# M514H.net
KiCad netlist of a schematic drawn in EAGLE
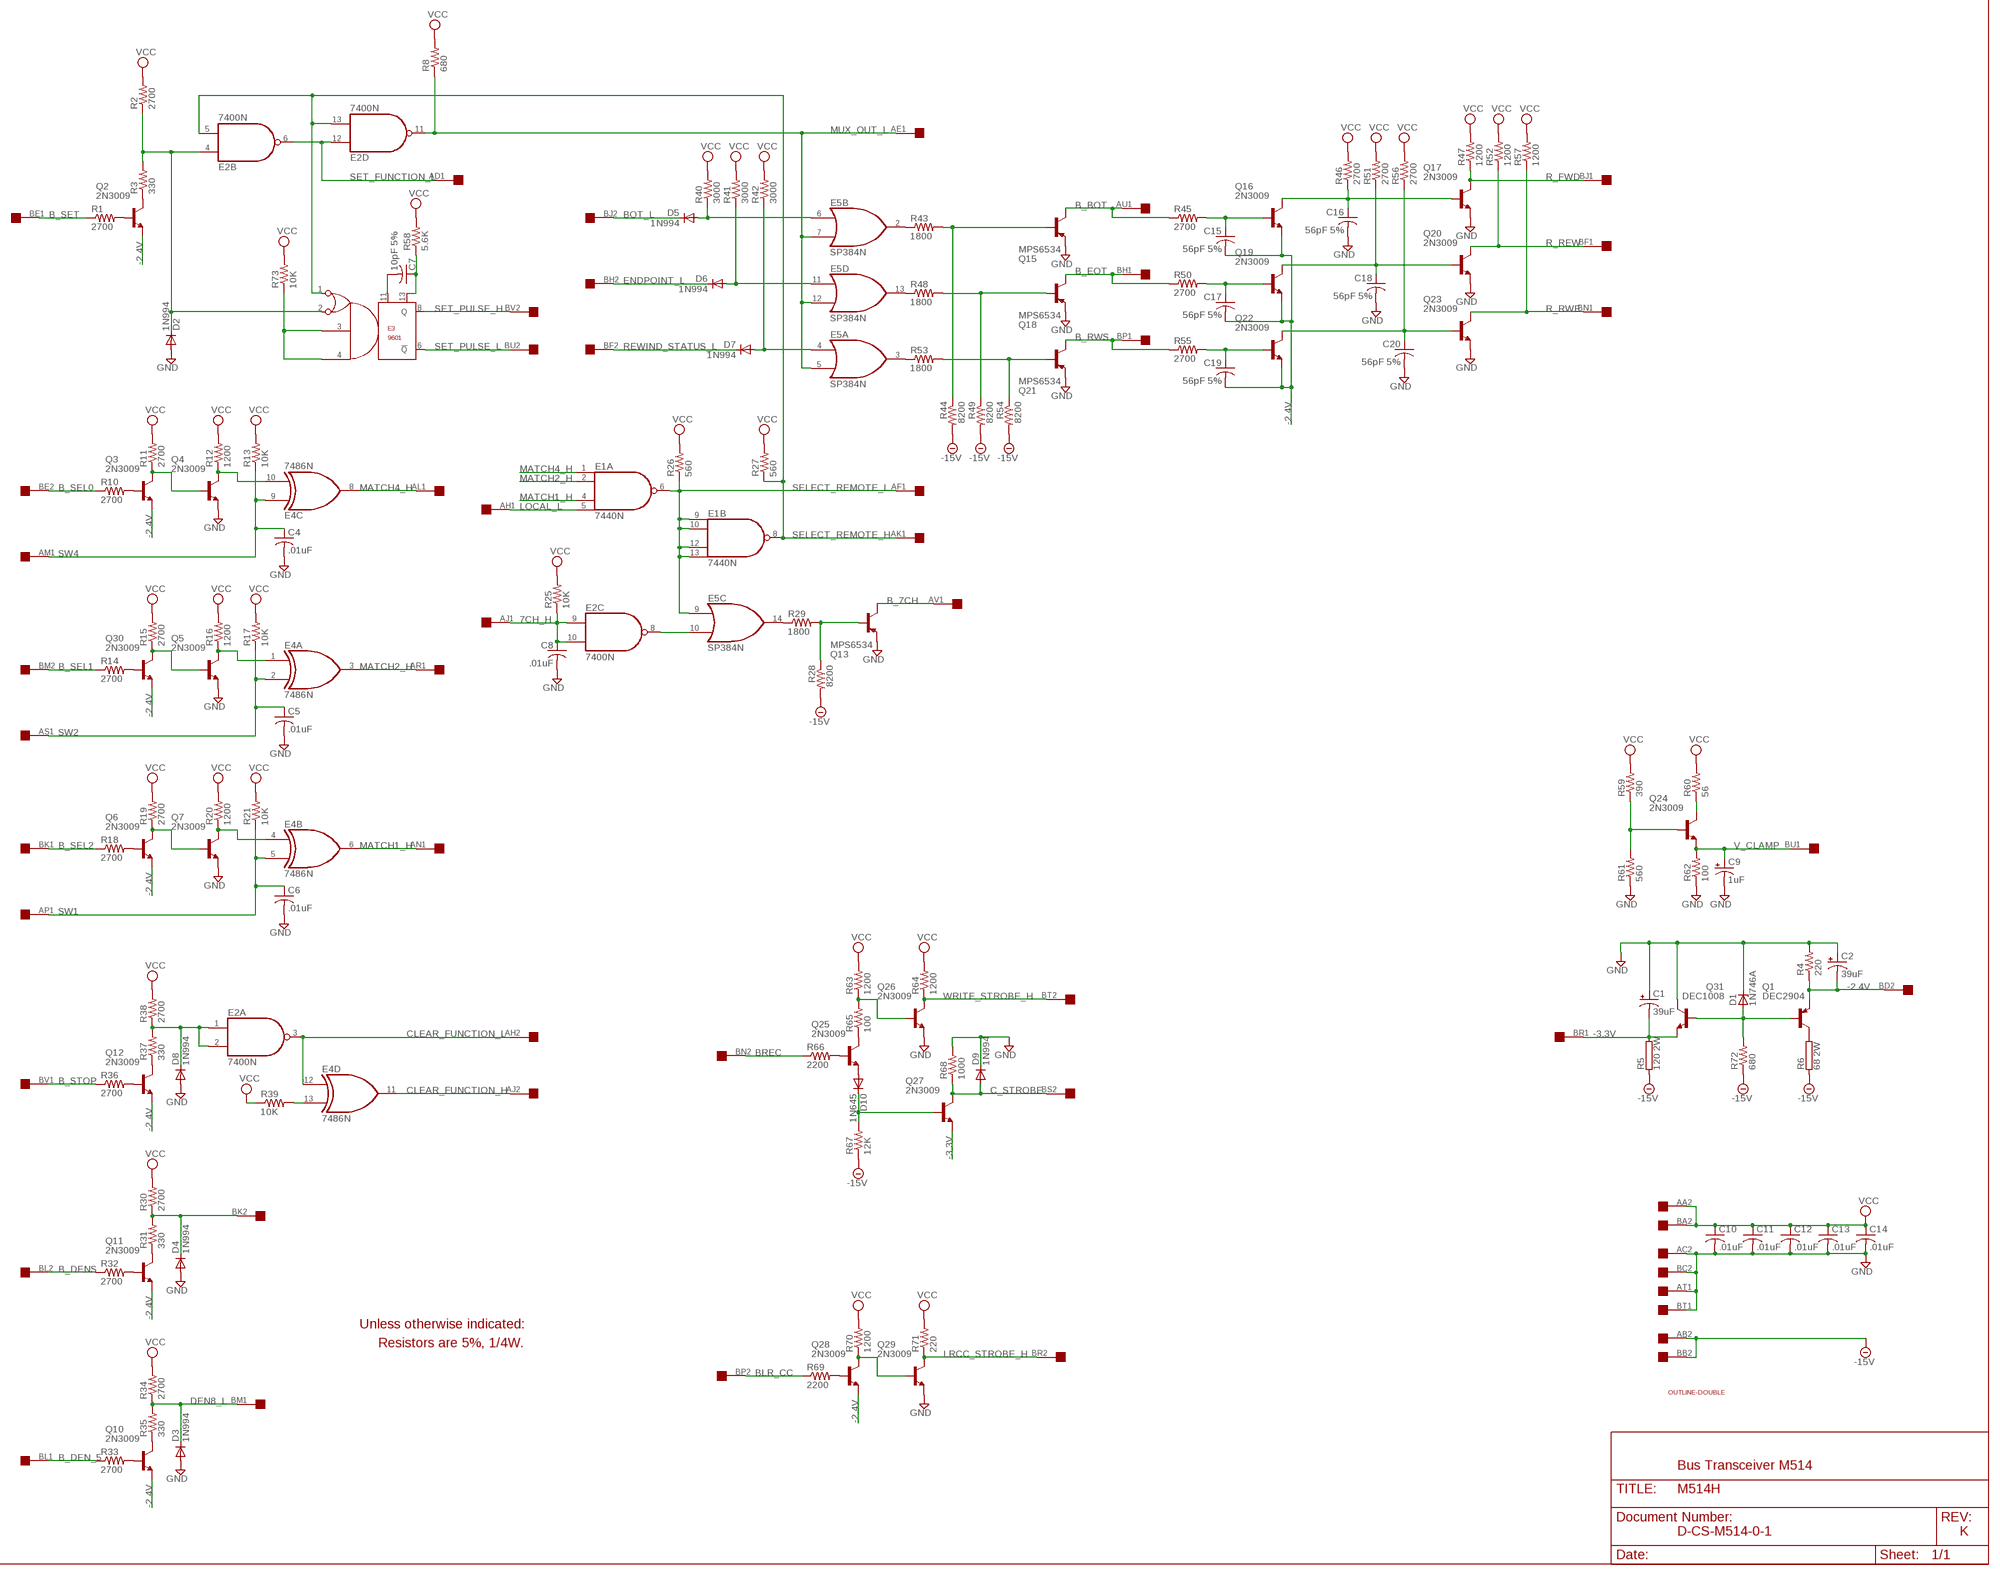
[diagram p0: schematic, sheet 1]

(export (version "E")
  (design (tool "Eeschema 10.0.6"))
  (components
    (comp (ref "C1")
      (value "39uF")
      (footprint "eagle-import:E12-8")
      (libsource (lib "eagle-import") (part "CPOL-USE20-8AXIAL"))
    )
    (comp (ref "C2")
      (value "39uF")
      (footprint "eagle-import:E12-8")
      (libsource (lib "eagle-import") (part "CPOL-USE20-8AXIAL"))
    )
    (comp (ref "C4")
      (value ".01uF")
      (footprint "eagle-import:C050-025X075")
      (libsource (lib "eagle-import") (part "C-US050-025X075"))
    )
    (comp (ref "C5")
      (value ".01uF")
      (footprint "eagle-import:C050-025X075")
      (libsource (lib "eagle-import") (part "C-US050-025X075"))
    )
    (comp (ref "C6")
      (value ".01uF")
      (footprint "eagle-import:C050-025X075")
      (libsource (lib "eagle-import") (part "C-US050-025X075"))
    )
    (comp (ref "C7")
      (value "10pF 5%")
      (footprint "eagle-import:C050-025X075")
      (libsource (lib "eagle-import") (part "C-US050-025X075"))
    )
    (comp (ref "C8")
      (value ".01uF")
      (footprint "eagle-import:C050-025X075")
      (libsource (lib "eagle-import") (part "C-US050-025X075"))
    )
    (comp (ref "C9")
      (value "1uF")
      (footprint "eagle-import:E15-5")
      (libsource (lib "eagle-import") (part "CPOL-USE15-5AXIAL"))
    )
    (comp (ref "C10")
      (value ".01uF")
      (footprint "eagle-import:C050-025X075")
      (libsource (lib "eagle-import") (part "C-US050-025X075"))
    )
    (comp (ref "C11")
      (value ".01uF")
      (footprint "eagle-import:C050-025X075")
      (libsource (lib "eagle-import") (part "C-US050-025X075"))
    )
    (comp (ref "C12")
      (value ".01uF")
      (footprint "eagle-import:C050-025X075")
      (libsource (lib "eagle-import") (part "C-US050-025X075"))
    )
    (comp (ref "C13")
      (value ".01uF")
      (footprint "eagle-import:C050-025X075")
      (libsource (lib "eagle-import") (part "C-US050-025X075"))
    )
    (comp (ref "C14")
      (value ".01uF")
      (footprint "eagle-import:C050-025X075")
      (libsource (lib "eagle-import") (part "C-US050-025X075"))
    )
    (comp (ref "C15")
      (value "56pF 5%")
      (footprint "eagle-import:C050-025X075")
      (libsource (lib "eagle-import") (part "C-US050-025X075"))
    )
    (comp (ref "C16")
      (value "56pF 5%")
      (footprint "eagle-import:C050-025X075")
      (libsource (lib "eagle-import") (part "C-US050-025X075"))
    )
    (comp (ref "C17")
      (value "56pF 5%")
      (footprint "eagle-import:C050-025X075")
      (libsource (lib "eagle-import") (part "C-US050-025X075"))
    )
    (comp (ref "C18")
      (value "56pF 5%")
      (footprint "eagle-import:C050-025X075")
      (libsource (lib "eagle-import") (part "C-US050-025X075"))
    )
    (comp (ref "C19")
      (value "56pF 5%")
      (footprint "eagle-import:C050-025X075")
      (libsource (lib "eagle-import") (part "C-US050-025X075"))
    )
    (comp (ref "C20")
      (value "56pF 5%")
      (footprint "eagle-import:C050-025X075")
      (libsource (lib "eagle-import") (part "C-US050-025X075"))
    )
    (comp (ref "D1")
      (value "1N746A")
      (footprint "eagle-import:DO35Z10")
      (libsource (lib "eagle-import") (part "ZENER-DIODEDO35Z10"))
    )
    (comp (ref "D2")
      (value "1N994")
      (footprint "eagle-import:DO35-10")
      (libsource (lib "eagle-import") (part "1N4148DO35-10"))
    )
    (comp (ref "D3")
      (value "1N994")
      (footprint "eagle-import:DO35-10")
      (libsource (lib "eagle-import") (part "1N4148DO35-10"))
    )
    (comp (ref "D4")
      (value "1N994")
      (footprint "eagle-import:DO35-10")
      (libsource (lib "eagle-import") (part "1N4148DO35-10"))
    )
    (comp (ref "D5")
      (value "1N994")
      (footprint "eagle-import:DO35-10")
      (libsource (lib "eagle-import") (part "1N4148DO35-10"))
    )
    (comp (ref "D6")
      (value "1N994")
      (footprint "eagle-import:DO35-10")
      (libsource (lib "eagle-import") (part "1N4148DO35-10"))
    )
    (comp (ref "D7")
      (value "1N994")
      (footprint "eagle-import:DO35-10")
      (libsource (lib "eagle-import") (part "1N4148DO35-10"))
    )
    (comp (ref "D8")
      (value "1N994")
      (footprint "eagle-import:DO35-10")
      (libsource (lib "eagle-import") (part "1N4148DO35-10"))
    )
    (comp (ref "D9")
      (value "1N994")
      (footprint "eagle-import:DO35-10")
      (libsource (lib "eagle-import") (part "1N4148DO35-10"))
    )
    (comp (ref "D10")
      (value "1N645")
      (footprint "eagle-import:DO35-10")
      (libsource (lib "eagle-import") (part "1N4148DO35-10"))
    )
    (comp (ref "E1")
      (value "7440N")
      (footprint "eagle-import:DIL14")
      (libsource (lib "eagle-import") (part "7420NS"))
    )
    (comp (ref "E2")
      (value "7400N")
      (footprint "eagle-import:DIL14")
      (libsource (lib "eagle-import") (part "7400N"))
    )
    (comp (ref "E3")
      (value "9601")
      (footprint "eagle-import:DIL14")
      (libsource (lib "eagle-import") (part "9601"))
    )
    (comp (ref "E4")
      (value "7486N")
      (footprint "eagle-import:DIL14")
      (libsource (lib "eagle-import") (part "7486N"))
    )
    (comp (ref "E5")
      (value "SP384N")
      (footprint "eagle-import:DIL14")
      (libsource (lib "eagle-import") (part "SP384N"))
    )
    (comp (ref "Q1")
      (value "DEC2904")
      (footprint "eagle-import:TO39")
      (libsource (lib "eagle-import") (part "2N3635"))
    )
    (comp (ref "Q2")
      (value "2N3009")
      (footprint "eagle-import:TO5")
      (libsource (lib "eagle-import") (part "2N3439"))
    )
    (comp (ref "Q3")
      (value "2N3009")
      (footprint "eagle-import:TO5")
      (libsource (lib "eagle-import") (part "2N3439"))
    )
    (comp (ref "Q4")
      (value "2N3009")
      (footprint "eagle-import:TO5")
      (libsource (lib "eagle-import") (part "2N3439"))
    )
    (comp (ref "Q5")
      (value "2N3009")
      (footprint "eagle-import:TO5")
      (libsource (lib "eagle-import") (part "2N3439"))
    )
    (comp (ref "Q6")
      (value "2N3009")
      (footprint "eagle-import:TO5")
      (libsource (lib "eagle-import") (part "2N3439"))
    )
    (comp (ref "Q7")
      (value "2N3009")
      (footprint "eagle-import:TO5")
      (libsource (lib "eagle-import") (part "2N3439"))
    )
    (comp (ref "Q10")
      (value "2N3009")
      (footprint "eagle-import:TO5")
      (libsource (lib "eagle-import") (part "2N3439"))
    )
    (comp (ref "Q11")
      (value "2N3009")
      (footprint "eagle-import:TO5")
      (libsource (lib "eagle-import") (part "2N3439"))
    )
    (comp (ref "Q12")
      (value "2N3009")
      (footprint "eagle-import:TO5")
      (libsource (lib "eagle-import") (part "2N3439"))
    )
    (comp (ref "Q13")
      (value "MPS6534")
      (footprint "eagle-import:TO39")
      (libsource (lib "eagle-import") (part "2N3635"))
    )
    (comp (ref "Q15")
      (value "MPS6534")
      (footprint "eagle-import:TO39")
      (libsource (lib "eagle-import") (part "2N3635"))
    )
    (comp (ref "Q16")
      (value "2N3009")
      (footprint "eagle-import:TO5")
      (libsource (lib "eagle-import") (part "2N3439"))
    )
    (comp (ref "Q17")
      (value "2N3009")
      (footprint "eagle-import:TO5")
      (libsource (lib "eagle-import") (part "2N3439"))
    )
    (comp (ref "Q18")
      (value "MPS6534")
      (footprint "eagle-import:TO39")
      (libsource (lib "eagle-import") (part "2N3635"))
    )
    (comp (ref "Q19")
      (value "2N3009")
      (footprint "eagle-import:TO5")
      (libsource (lib "eagle-import") (part "2N3439"))
    )
    (comp (ref "Q20")
      (value "2N3009")
      (footprint "eagle-import:TO5")
      (libsource (lib "eagle-import") (part "2N3439"))
    )
    (comp (ref "Q21")
      (value "MPS6534")
      (footprint "eagle-import:TO39")
      (libsource (lib "eagle-import") (part "2N3635"))
    )
    (comp (ref "Q22")
      (value "2N3009")
      (footprint "eagle-import:TO5")
      (libsource (lib "eagle-import") (part "2N3439"))
    )
    (comp (ref "Q23")
      (value "2N3009")
      (footprint "eagle-import:TO5")
      (libsource (lib "eagle-import") (part "2N3439"))
    )
    (comp (ref "Q24")
      (value "2N3009")
      (footprint "eagle-import:TO5")
      (libsource (lib "eagle-import") (part "2N3439"))
    )
    (comp (ref "Q25")
      (value "2N3009")
      (footprint "eagle-import:TO5")
      (libsource (lib "eagle-import") (part "2N3439"))
    )
    (comp (ref "Q26")
      (value "2N3009")
      (footprint "eagle-import:TO5")
      (libsource (lib "eagle-import") (part "2N3439"))
    )
    (comp (ref "Q27")
      (value "2N3009")
      (footprint "eagle-import:TO5")
      (libsource (lib "eagle-import") (part "2N3439"))
    )
    (comp (ref "Q28")
      (value "2N3009")
      (footprint "eagle-import:TO5")
      (libsource (lib "eagle-import") (part "2N3439"))
    )
    (comp (ref "Q29")
      (value "2N3009")
      (footprint "eagle-import:TO5")
      (libsource (lib "eagle-import") (part "2N3439"))
    )
    (comp (ref "Q30")
      (value "2N3009")
      (footprint "eagle-import:TO5")
      (libsource (lib "eagle-import") (part "2N3439"))
    )
    (comp (ref "Q31")
      (value "DEC1008")
      (footprint "eagle-import:TO5")
      (libsource (lib "eagle-import") (part "2N3439"))
    )
    (comp (ref "R1")
      (value "2700")
      (footprint "eagle-import:0207_10")
      (libsource (lib "eagle-import") (part "R-US_0207/10"))
    )
    (comp (ref "R2")
      (value "2700")
      (footprint "eagle-import:0207_10")
      (libsource (lib "eagle-import") (part "R-US_0207/10"))
    )
    (comp (ref "R3")
      (value "330")
      (footprint "eagle-import:0207_10")
      (libsource (lib "eagle-import") (part "R-US_0207/10"))
    )
    (comp (ref "R4")
      (value "220")
      (footprint "eagle-import:0207_10")
      (libsource (lib "eagle-import") (part "R-US_0207/10"))
    )
    (comp (ref "R5")
      (value "120 2W")
      (footprint "eagle-import:KH206-8")
      (libsource (lib "eagle-import") (part "RKH206-8"))
    )
    (comp (ref "R6")
      (value "68 2W")
      (footprint "eagle-import:KH206-8")
      (libsource (lib "eagle-import") (part "RKH206-8"))
    )
    (comp (ref "R8")
      (value "680")
      (footprint "eagle-import:0207_10")
      (libsource (lib "eagle-import") (part "R-US_0207/10"))
    )
    (comp (ref "R10")
      (value "2700")
      (footprint "eagle-import:0207_10")
      (libsource (lib "eagle-import") (part "R-US_0207/10"))
    )
    (comp (ref "R11")
      (value "2700")
      (footprint "eagle-import:0207_10")
      (libsource (lib "eagle-import") (part "R-US_0207/10"))
    )
    (comp (ref "R12")
      (value "1200")
      (footprint "eagle-import:0207_10")
      (libsource (lib "eagle-import") (part "R-US_0207/10"))
    )
    (comp (ref "R13")
      (value "10K")
      (footprint "eagle-import:0207_10")
      (libsource (lib "eagle-import") (part "R-US_0207/10"))
    )
    (comp (ref "R14")
      (value "2700")
      (footprint "eagle-import:0207_10")
      (libsource (lib "eagle-import") (part "R-US_0207/10"))
    )
    (comp (ref "R15")
      (value "2700")
      (footprint "eagle-import:0207_10")
      (libsource (lib "eagle-import") (part "R-US_0207/10"))
    )
    (comp (ref "R16")
      (value "1200")
      (footprint "eagle-import:0207_10")
      (libsource (lib "eagle-import") (part "R-US_0207/10"))
    )
    (comp (ref "R17")
      (value "10K")
      (footprint "eagle-import:0207_10")
      (libsource (lib "eagle-import") (part "R-US_0207/10"))
    )
    (comp (ref "R18")
      (value "2700")
      (footprint "eagle-import:0207_10")
      (libsource (lib "eagle-import") (part "R-US_0207/10"))
    )
    (comp (ref "R19")
      (value "2700")
      (footprint "eagle-import:0207_10")
      (libsource (lib "eagle-import") (part "R-US_0207/10"))
    )
    (comp (ref "R20")
      (value "1200")
      (footprint "eagle-import:0207_10")
      (libsource (lib "eagle-import") (part "R-US_0207/10"))
    )
    (comp (ref "R21")
      (value "10K")
      (footprint "eagle-import:0207_10")
      (libsource (lib "eagle-import") (part "R-US_0207/10"))
    )
    (comp (ref "R25")
      (value "10K")
      (footprint "eagle-import:0207_10")
      (libsource (lib "eagle-import") (part "R-US_0207/10"))
    )
    (comp (ref "R26")
      (value "560")
      (footprint "eagle-import:0207_10")
      (libsource (lib "eagle-import") (part "R-US_0207/10"))
    )
    (comp (ref "R27")
      (value "560")
      (footprint "eagle-import:0207_10")
      (libsource (lib "eagle-import") (part "R-US_0207/10"))
    )
    (comp (ref "R28")
      (value "8200")
      (footprint "eagle-import:0207_10")
      (libsource (lib "eagle-import") (part "R-US_0207/10"))
    )
    (comp (ref "R29")
      (value "1800")
      (footprint "eagle-import:0207_10")
      (libsource (lib "eagle-import") (part "R-US_0207/10"))
    )
    (comp (ref "R30")
      (value "2700")
      (footprint "eagle-import:0207_10")
      (libsource (lib "eagle-import") (part "R-US_0207/10"))
    )
    (comp (ref "R31")
      (value "330")
      (footprint "eagle-import:0207_10")
      (libsource (lib "eagle-import") (part "R-US_0207/10"))
    )
    (comp (ref "R32")
      (value "2700")
      (footprint "eagle-import:0207_10")
      (libsource (lib "eagle-import") (part "R-US_0207/10"))
    )
    (comp (ref "R33")
      (value "2700")
      (footprint "eagle-import:0207_10")
      (libsource (lib "eagle-import") (part "R-US_0207/10"))
    )
    (comp (ref "R34")
      (value "2700")
      (footprint "eagle-import:0207_10")
      (libsource (lib "eagle-import") (part "R-US_0207/10"))
    )
    (comp (ref "R35")
      (value "330")
      (footprint "eagle-import:0207_10")
      (libsource (lib "eagle-import") (part "R-US_0207/10"))
    )
    (comp (ref "R36")
      (value "2700")
      (footprint "eagle-import:0207_10")
      (libsource (lib "eagle-import") (part "R-US_0207/10"))
    )
    (comp (ref "R37")
      (value "330")
      (footprint "eagle-import:0207_10")
      (libsource (lib "eagle-import") (part "R-US_0207/10"))
    )
    (comp (ref "R38")
      (value "2700")
      (footprint "eagle-import:0207_10")
      (libsource (lib "eagle-import") (part "R-US_0207/10"))
    )
    (comp (ref "R39")
      (value "10K")
      (footprint "eagle-import:0207_10")
      (libsource (lib "eagle-import") (part "R-US_0207/10"))
    )
    (comp (ref "R40")
      (value "3000")
      (footprint "eagle-import:0207_10")
      (libsource (lib "eagle-import") (part "R-US_0207/10"))
    )
    (comp (ref "R41")
      (value "3000")
      (footprint "eagle-import:0207_10")
      (libsource (lib "eagle-import") (part "R-US_0207/10"))
    )
    (comp (ref "R42")
      (value "3000")
      (footprint "eagle-import:0207_10")
      (libsource (lib "eagle-import") (part "R-US_0207/10"))
    )
    (comp (ref "R43")
      (value "1800")
      (footprint "eagle-import:0207_10")
      (libsource (lib "eagle-import") (part "R-US_0207/10"))
    )
    (comp (ref "R44")
      (value "8200")
      (footprint "eagle-import:0207_10")
      (libsource (lib "eagle-import") (part "R-US_0207/10"))
    )
    (comp (ref "R45")
      (value "2700")
      (footprint "eagle-import:0207_10")
      (libsource (lib "eagle-import") (part "R-US_0207/10"))
    )
    (comp (ref "R46")
      (value "2700")
      (footprint "eagle-import:0207_10")
      (libsource (lib "eagle-import") (part "R-US_0207/10"))
    )
    (comp (ref "R47")
      (value "1200")
      (footprint "eagle-import:0207_10")
      (libsource (lib "eagle-import") (part "R-US_0207/10"))
    )
    (comp (ref "R48")
      (value "1800")
      (footprint "eagle-import:0207_10")
      (libsource (lib "eagle-import") (part "R-US_0207/10"))
    )
    (comp (ref "R49")
      (value "8200")
      (footprint "eagle-import:0207_10")
      (libsource (lib "eagle-import") (part "R-US_0207/10"))
    )
    (comp (ref "R50")
      (value "2700")
      (footprint "eagle-import:0207_10")
      (libsource (lib "eagle-import") (part "R-US_0207/10"))
    )
    (comp (ref "R51")
      (value "2700")
      (footprint "eagle-import:0207_10")
      (libsource (lib "eagle-import") (part "R-US_0207/10"))
    )
    (comp (ref "R52")
      (value "1200")
      (footprint "eagle-import:0207_10")
      (libsource (lib "eagle-import") (part "R-US_0207/10"))
    )
    (comp (ref "R53")
      (value "1800")
      (footprint "eagle-import:0207_10")
      (libsource (lib "eagle-import") (part "R-US_0207/10"))
    )
    (comp (ref "R54")
      (value "8200")
      (footprint "eagle-import:0207_10")
      (libsource (lib "eagle-import") (part "R-US_0207/10"))
    )
    (comp (ref "R55")
      (value "2700")
      (footprint "eagle-import:0207_10")
      (libsource (lib "eagle-import") (part "R-US_0207/10"))
    )
    (comp (ref "R56")
      (value "2700")
      (footprint "eagle-import:0207_10")
      (libsource (lib "eagle-import") (part "R-US_0207/10"))
    )
    (comp (ref "R57")
      (value "1200")
      (footprint "eagle-import:0207_10")
      (libsource (lib "eagle-import") (part "R-US_0207/10"))
    )
    (comp (ref "R58")
      (value "5.6K")
      (footprint "eagle-import:0207_10")
      (libsource (lib "eagle-import") (part "R-US_0207/10"))
    )
    (comp (ref "R59")
      (value "390")
      (footprint "eagle-import:0207_10")
      (libsource (lib "eagle-import") (part "R-US_0207/10"))
    )
    (comp (ref "R60")
      (value "56")
      (footprint "eagle-import:0207_10")
      (libsource (lib "eagle-import") (part "R-US_0207/10"))
    )
    (comp (ref "R61")
      (value "560")
      (footprint "eagle-import:0207_10")
      (libsource (lib "eagle-import") (part "R-US_0207/10"))
    )
    (comp (ref "R62")
      (value "100")
      (footprint "eagle-import:0207_10")
      (libsource (lib "eagle-import") (part "R-US_0207/10"))
    )
    (comp (ref "R63")
      (value "1200")
      (footprint "eagle-import:0207_10")
      (libsource (lib "eagle-import") (part "R-US_0207/10"))
    )
    (comp (ref "R64")
      (value "1200")
      (footprint "eagle-import:0207_10")
      (libsource (lib "eagle-import") (part "R-US_0207/10"))
    )
    (comp (ref "R65")
      (value "100")
      (footprint "eagle-import:0207_10")
      (libsource (lib "eagle-import") (part "R-US_0207/10"))
    )
    (comp (ref "R66")
      (value "2200")
      (footprint "eagle-import:0207_10")
      (libsource (lib "eagle-import") (part "R-US_0207/10"))
    )
    (comp (ref "R67")
      (value "12K")
      (footprint "eagle-import:0207_10")
      (libsource (lib "eagle-import") (part "R-US_0207/10"))
    )
    (comp (ref "R68")
      (value "1000")
      (footprint "eagle-import:0207_10")
      (libsource (lib "eagle-import") (part "R-US_0207/10"))
    )
    (comp (ref "R69")
      (value "2200")
      (footprint "eagle-import:0207_10")
      (libsource (lib "eagle-import") (part "R-US_0207/10"))
    )
    (comp (ref "R70")
      (value "1200")
      (footprint "eagle-import:0207_10")
      (libsource (lib "eagle-import") (part "R-US_0207/10"))
    )
    (comp (ref "R71")
      (value "220")
      (footprint "eagle-import:0207_10")
      (libsource (lib "eagle-import") (part "R-US_0207/10"))
    )
    (comp (ref "R72")
      (value "680")
      (footprint "eagle-import:0207_10")
      (libsource (lib "eagle-import") (part "R-US_0207/10"))
    )
    (comp (ref "R73")
      (value "10K")
      (footprint "eagle-import:0207_10")
      (libsource (lib "eagle-import") (part "R-US_0207/10"))
    )
    (comp (ref "U$1")
      (value "DOUBLE")
      (footprint "eagle-import:EDGE-CON4")
      (libsource (lib "eagle-import") (part "DOUBLE"))
    )
    (comp (ref "U$2")
      (value "OUTLINE-DOUBLE")
      (footprint "eagle-import:DOUBLE")
      (libsource (lib "eagle-import") (part "OUTLINE-DOUBLE"))
    )
  )
  (nets
    (net (code "1") (name "-15V") (class "Default")
      (node (ref "R28") (pin "2") (pinfunction "2_2") (pintype "passive"))
      (node (ref "R44") (pin "2") (pinfunction "2_2") (pintype "passive"))
      (node (ref "R49") (pin "2") (pinfunction "2_2") (pintype "passive"))
      (node (ref "R5") (pin "1") (pinfunction "1_1") (pintype "passive"))
      (node (ref "R54") (pin "2") (pinfunction "2_2") (pintype "passive"))
      (node (ref "R6") (pin "1") (pinfunction "1_1") (pintype "passive"))
      (node (ref "R67") (pin "1") (pinfunction "1_1") (pintype "passive"))
      (node (ref "R72") (pin "1") (pinfunction "1_1") (pintype "passive"))
      (node (ref "U$1") (pin "AB2") (pinfunction "1_AB2") (pintype "bidirectional"))
      (node (ref "U$1") (pin "BB2") (pinfunction "1_BB2") (pintype "bidirectional"))
    )
    (net (code "2") (name "/-2.4V") (class "Default")
      (node (ref "C15") (pin "2") (pinfunction "2_2") (pintype "passive"))
      (node (ref "C17") (pin "2") (pinfunction "2_2") (pintype "passive"))
      (node (ref "C19") (pin "2") (pinfunction "2_2") (pintype "passive"))
      (node (ref "C2") (pin "-") (pinfunction "-_-") (pintype "passive"))
      (node (ref "Q1") (pin "1") (pinfunction "E_1") (pintype "passive"))
      (node (ref "Q10") (pin "1") (pinfunction "E_1") (pintype "passive"))
      (node (ref "Q11") (pin "1") (pinfunction "E_1") (pintype "passive"))
      (node (ref "Q12") (pin "1") (pinfunction "E_1") (pintype "passive"))
      (node (ref "Q16") (pin "1") (pinfunction "E_1") (pintype "passive"))
      (node (ref "Q19") (pin "1") (pinfunction "E_1") (pintype "passive"))
      (node (ref "Q2") (pin "1") (pinfunction "E_1") (pintype "passive"))
      (node (ref "Q22") (pin "1") (pinfunction "E_1") (pintype "passive"))
      (node (ref "Q28") (pin "1") (pinfunction "E_1") (pintype "passive"))
      (node (ref "Q3") (pin "1") (pinfunction "E_1") (pintype "passive"))
      (node (ref "Q30") (pin "1") (pinfunction "E_1") (pintype "passive"))
      (node (ref "Q6") (pin "1") (pinfunction "E_1") (pintype "passive"))
      (node (ref "R4") (pin "1") (pinfunction "1_1") (pintype "passive"))
      (node (ref "U$1") (pin "BD2") (pinfunction "1_BD2") (pintype "bidirectional"))
    )
    (net (code "3") (name "/-3.3V") (class "Default")
      (node (ref "C1") (pin "-") (pinfunction "-_-") (pintype "passive"))
      (node (ref "Q27") (pin "1") (pinfunction "E_1") (pintype "passive"))
      (node (ref "Q31") (pin "1") (pinfunction "E_1") (pintype "passive"))
      (node (ref "R5") (pin "2") (pinfunction "2_2") (pintype "passive"))
      (node (ref "U$1") (pin "BR1") (pinfunction "1_BR1") (pintype "bidirectional"))
    )
    (net (code "4") (name "/7CH_H") (class "Default")
      (node (ref "C8") (pin "1") (pinfunction "1_1") (pintype "passive"))
      (node (ref "E2") (pin "10") (pinfunction "I1_10") (pintype "input"))
      (node (ref "E2") (pin "9") (pinfunction "I0_9") (pintype "input"))
      (node (ref "R25") (pin "1") (pinfunction "1_1") (pintype "passive"))
      (node (ref "U$1") (pin "AJ1") (pinfunction "1_AJ1") (pintype "bidirectional"))
    )
    (net (code "5") (name "/BLR_CC") (class "Default")
      (node (ref "R69") (pin "1") (pinfunction "1_1") (pintype "passive"))
      (node (ref "U$1") (pin "BP2") (pinfunction "1_BP2") (pintype "bidirectional"))
    )
    (net (code "6") (name "/BOT_L") (class "Default")
      (node (ref "D5") (pin "C") (pinfunction "C_C") (pintype "passive"))
      (node (ref "U$1") (pin "BJ2") (pinfunction "1_BJ2") (pintype "bidirectional"))
    )
    (net (code "7") (name "/BREC") (class "Default")
      (node (ref "R66") (pin "1") (pinfunction "1_1") (pintype "passive"))
      (node (ref "U$1") (pin "BN2") (pinfunction "1_BN2") (pintype "bidirectional"))
    )
    (net (code "8") (name "/B_7CH") (class "Default")
      (node (ref "Q13") (pin "3") (pinfunction "C_3") (pintype "passive"))
      (node (ref "U$1") (pin "AV1") (pinfunction "1_AV1") (pintype "bidirectional"))
    )
    (net (code "9") (name "/B_BOT") (class "Default")
      (node (ref "Q15") (pin "3") (pinfunction "C_3") (pintype "passive"))
      (node (ref "R45") (pin "1") (pinfunction "1_1") (pintype "passive"))
      (node (ref "U$1") (pin "AU1") (pinfunction "1_AU1") (pintype "bidirectional"))
    )
    (net (code "10") (name "/B_DENS") (class "Default")
      (node (ref "R32") (pin "1") (pinfunction "1_1") (pintype "passive"))
      (node (ref "U$1") (pin "BL2") (pinfunction "1_BL2") (pintype "bidirectional"))
    )
    (net (code "11") (name "/B_DEN_5") (class "Default")
      (node (ref "R33") (pin "1") (pinfunction "1_1") (pintype "passive"))
      (node (ref "U$1") (pin "BL1") (pinfunction "1_BL1") (pintype "bidirectional"))
    )
    (net (code "12") (name "/B_EOT") (class "Default")
      (node (ref "Q18") (pin "3") (pinfunction "C_3") (pintype "passive"))
      (node (ref "R50") (pin "1") (pinfunction "1_1") (pintype "passive"))
      (node (ref "U$1") (pin "BH1") (pinfunction "1_BH1") (pintype "bidirectional"))
    )
    (net (code "13") (name "/B_RWS") (class "Default")
      (node (ref "Q21") (pin "3") (pinfunction "C_3") (pintype "passive"))
      (node (ref "R55") (pin "1") (pinfunction "1_1") (pintype "passive"))
      (node (ref "U$1") (pin "BP1") (pinfunction "1_BP1") (pintype "bidirectional"))
    )
    (net (code "14") (name "/B_SEL0") (class "Default")
      (node (ref "R10") (pin "1") (pinfunction "1_1") (pintype "passive"))
      (node (ref "U$1") (pin "BE2") (pinfunction "1_BE2") (pintype "bidirectional"))
    )
    (net (code "15") (name "/B_SEL1") (class "Default")
      (node (ref "R14") (pin "1") (pinfunction "1_1") (pintype "passive"))
      (node (ref "U$1") (pin "BM2") (pinfunction "1_BM2") (pintype "bidirectional"))
    )
    (net (code "16") (name "/B_SEL2") (class "Default")
      (node (ref "R18") (pin "1") (pinfunction "1_1") (pintype "passive"))
      (node (ref "U$1") (pin "BK1") (pinfunction "1_BK1") (pintype "bidirectional"))
    )
    (net (code "17") (name "/B_SET") (class "Default")
      (node (ref "R1") (pin "1") (pinfunction "1_1") (pintype "passive"))
      (node (ref "U$1") (pin "BE1") (pinfunction "1_BE1") (pintype "bidirectional"))
    )
    (net (code "18") (name "/B_STOP") (class "Default")
      (node (ref "R36") (pin "1") (pinfunction "1_1") (pintype "passive"))
      (node (ref "U$1") (pin "BV1") (pinfunction "1_BV1") (pintype "bidirectional"))
    )
    (net (code "19") (name "/CLEAR_FUNCTION_H") (class "Default")
      (node (ref "E4") (pin "11") (pinfunction "O_11") (pintype "output"))
      (node (ref "U$1") (pin "AJ2") (pinfunction "1_AJ2") (pintype "bidirectional"))
    )
    (net (code "20") (name "/CLEAR_FUNCTION_L") (class "Default")
      (node (ref "E2") (pin "3") (pinfunction "O_3") (pintype "output"))
      (node (ref "E4") (pin "12") (pinfunction "I0_12") (pintype "input"))
      (node (ref "U$1") (pin "AH2") (pinfunction "1_AH2") (pintype "bidirectional"))
    )
    (net (code "21") (name "/C_STROBE") (class "Default")
      (node (ref "D9") (pin "A") (pinfunction "A_A") (pintype "passive"))
      (node (ref "Q27") (pin "3") (pinfunction "C_3") (pintype "passive"))
      (node (ref "R68") (pin "1") (pinfunction "1_1") (pintype "passive"))
      (node (ref "U$1") (pin "BS2") (pinfunction "1_BS2") (pintype "bidirectional"))
    )
    (net (code "22") (name "/DEN8_L") (class "Default")
      (node (ref "D3") (pin "C") (pinfunction "C_C") (pintype "passive"))
      (node (ref "R34") (pin "1") (pinfunction "1_1") (pintype "passive"))
      (node (ref "R35") (pin "2") (pinfunction "2_2") (pintype "passive"))
      (node (ref "U$1") (pin "BM1") (pinfunction "1_BM1") (pintype "bidirectional"))
    )
    (net (code "23") (name "/ENDPOINT_L") (class "Default")
      (node (ref "D6") (pin "C") (pinfunction "C_C") (pintype "passive"))
      (node (ref "U$1") (pin "BH2") (pinfunction "1_BH2") (pintype "bidirectional"))
    )
    (net (code "24") (name "/LOCAL_L") (class "Default")
      (node (ref "E1") (pin "5") (pinfunction "I3_5") (pintype "input"))
      (node (ref "U$1") (pin "AH1") (pinfunction "1_AH1") (pintype "bidirectional"))
    )
    (net (code "25") (name "/LRCC_STROBE_H") (class "Default")
      (node (ref "Q29") (pin "3") (pinfunction "C_3") (pintype "passive"))
      (node (ref "R71") (pin "1") (pinfunction "1_1") (pintype "passive"))
      (node (ref "U$1") (pin "BR2") (pinfunction "1_BR2") (pintype "bidirectional"))
    )
    (net (code "26") (name "/MATCH1_H") (class "Default")
      (node (ref "E1") (pin "4") (pinfunction "I2_4") (pintype "input"))
      (node (ref "E4") (pin "6") (pinfunction "O_6") (pintype "output"))
      (node (ref "U$1") (pin "AN1") (pinfunction "1_AN1") (pintype "bidirectional"))
    )
    (net (code "27") (name "/MATCH2_H") (class "Default")
      (node (ref "E1") (pin "2") (pinfunction "I1_2") (pintype "input"))
      (node (ref "E4") (pin "3") (pinfunction "O_3") (pintype "output"))
      (node (ref "U$1") (pin "AR1") (pinfunction "1_AR1") (pintype "bidirectional"))
    )
    (net (code "28") (name "/MATCH4_H") (class "Default")
      (node (ref "E1") (pin "1") (pinfunction "I0_1") (pintype "input"))
      (node (ref "E4") (pin "8") (pinfunction "O_8") (pintype "output"))
      (node (ref "U$1") (pin "AL1") (pinfunction "1_AL1") (pintype "bidirectional"))
    )
    (net (code "29") (name "/MUX_OUT_L") (class "Default")
      (node (ref "E2") (pin "11") (pinfunction "O_11") (pintype "output"))
      (node (ref "E5") (pin "12") (pinfunction "I1_12") (pintype "input"))
      (node (ref "E5") (pin "5") (pinfunction "I1_5") (pintype "input"))
      (node (ref "E5") (pin "7") (pinfunction "I1_7") (pintype "input"))
      (node (ref "R8") (pin "1") (pinfunction "1_1") (pintype "passive"))
      (node (ref "U$1") (pin "AE1") (pinfunction "1_AE1") (pintype "bidirectional"))
    )
    (net (code "30") (name "/REWIND_STATUS_L") (class "Default")
      (node (ref "D7") (pin "C") (pinfunction "C_C") (pintype "passive"))
      (node (ref "U$1") (pin "BF2") (pinfunction "1_BF2") (pintype "bidirectional"))
    )
    (net (code "31") (name "/R_FWD") (class "Default")
      (node (ref "Q17") (pin "3") (pinfunction "C_3") (pintype "passive"))
      (node (ref "R47") (pin "1") (pinfunction "1_1") (pintype "passive"))
      (node (ref "U$1") (pin "BJ1") (pinfunction "1_BJ1") (pintype "bidirectional"))
    )
    (net (code "32") (name "/R_REW") (class "Default")
      (node (ref "Q20") (pin "3") (pinfunction "C_3") (pintype "passive"))
      (node (ref "R52") (pin "1") (pinfunction "1_1") (pintype "passive"))
      (node (ref "U$1") (pin "BF1") (pinfunction "1_BF1") (pintype "bidirectional"))
    )
    (net (code "33") (name "/R_RWE") (class "Default")
      (node (ref "Q23") (pin "3") (pinfunction "C_3") (pintype "passive"))
      (node (ref "R57") (pin "1") (pinfunction "1_1") (pintype "passive"))
      (node (ref "U$1") (pin "BN1") (pinfunction "1_BN1") (pintype "bidirectional"))
    )
    (net (code "34") (name "/SELECT_REMOTE_H") (class "Default")
      (node (ref "E1") (pin "8") (pinfunction "O_8") (pintype "output"))
      (node (ref "E2") (pin "13") (pinfunction "I1_13") (pintype "input"))
      (node (ref "E2") (pin "5") (pinfunction "I1_5") (pintype "input"))
      (node (ref "E3") (pin "1") (pinfunction "P$1_1") (pintype "input"))
      (node (ref "R27") (pin "1") (pinfunction "1_1") (pintype "passive"))
      (node (ref "U$1") (pin "AK1") (pinfunction "1_AK1") (pintype "bidirectional"))
    )
    (net (code "35") (name "/SELECT_REMOTE_L") (class "Default")
      (node (ref "E1") (pin "10") (pinfunction "I1_10") (pintype "input"))
      (node (ref "E1") (pin "12") (pinfunction "I2_12") (pintype "input"))
      (node (ref "E1") (pin "13") (pinfunction "I3_13") (pintype "input"))
      (node (ref "E1") (pin "6") (pinfunction "O_6") (pintype "output"))
      (node (ref "E1") (pin "9") (pinfunction "I0_9") (pintype "input"))
      (node (ref "E5") (pin "9") (pinfunction "I0_9") (pintype "input"))
      (node (ref "R26") (pin "1") (pinfunction "1_1") (pintype "passive"))
      (node (ref "U$1") (pin "AF1") (pinfunction "1_AF1") (pintype "bidirectional"))
    )
    (net (code "36") (name "/SET_FUNCTION_L") (class "Default")
      (node (ref "E2") (pin "12") (pinfunction "I0_12") (pintype "input"))
      (node (ref "E2") (pin "6") (pinfunction "O_6") (pintype "output"))
      (node (ref "U$1") (pin "AD1") (pinfunction "1_AD1") (pintype "bidirectional"))
    )
    (net (code "37") (name "/SET_PULSE_H") (class "Default")
      (node (ref "E3") (pin "8") (pinfunction "Q_8") (pintype "output"))
      (node (ref "U$1") (pin "BV2") (pinfunction "1_BV2") (pintype "bidirectional"))
    )
    (net (code "38") (name "/SET_PULSE_L") (class "Default")
      (node (ref "E3") (pin "6") (pinfunction "~{Q}_6") (pintype "output"))
      (node (ref "U$1") (pin "BU2") (pinfunction "1_BU2") (pintype "bidirectional"))
    )
    (net (code "39") (name "/SW1") (class "Default")
      (node (ref "C6") (pin "1") (pinfunction "1_1") (pintype "passive"))
      (node (ref "E4") (pin "5") (pinfunction "I1_5") (pintype "input"))
      (node (ref "R21") (pin "1") (pinfunction "1_1") (pintype "passive"))
      (node (ref "U$1") (pin "AP1") (pinfunction "1_AP1") (pintype "bidirectional"))
    )
    (net (code "40") (name "/SW2") (class "Default")
      (node (ref "C5") (pin "1") (pinfunction "1_1") (pintype "passive"))
      (node (ref "E4") (pin "2") (pinfunction "I1_2") (pintype "input"))
      (node (ref "R17") (pin "1") (pinfunction "1_1") (pintype "passive"))
      (node (ref "U$1") (pin "AS1") (pinfunction "1_AS1") (pintype "bidirectional"))
    )
    (net (code "41") (name "/SW4") (class "Default")
      (node (ref "C4") (pin "1") (pinfunction "1_1") (pintype "passive"))
      (node (ref "E4") (pin "9") (pinfunction "I0_9") (pintype "input"))
      (node (ref "R13") (pin "1") (pinfunction "1_1") (pintype "passive"))
      (node (ref "U$1") (pin "AM1") (pinfunction "1_AM1") (pintype "bidirectional"))
    )
    (net (code "42") (name "/V_CLAMP") (class "Default")
      (node (ref "C9") (pin "+") (pinfunction "+_+") (pintype "passive"))
      (node (ref "Q24") (pin "1") (pinfunction "E_1") (pintype "passive"))
      (node (ref "R62") (pin "2") (pinfunction "2_2") (pintype "passive"))
      (node (ref "U$1") (pin "BU1") (pinfunction "1_BU1") (pintype "bidirectional"))
    )
    (net (code "43") (name "/WRITE_STROBE_H") (class "Default")
      (node (ref "Q26") (pin "3") (pinfunction "C_3") (pintype "passive"))
      (node (ref "R64") (pin "1") (pinfunction "1_1") (pintype "passive"))
      (node (ref "U$1") (pin "BT2") (pinfunction "1_BT2") (pintype "bidirectional"))
    )
    (net (code "44") (name "GND") (class "Default")
      (node (ref "C1") (pin "+") (pinfunction "+_+") (pintype "passive"))
      (node (ref "C10") (pin "2") (pinfunction "2_2") (pintype "passive"))
      (node (ref "C11") (pin "2") (pinfunction "2_2") (pintype "passive"))
      (node (ref "C12") (pin "2") (pinfunction "2_2") (pintype "passive"))
      (node (ref "C13") (pin "2") (pinfunction "2_2") (pintype "passive"))
      (node (ref "C14") (pin "2") (pinfunction "2_2") (pintype "passive"))
      (node (ref "C16") (pin "2") (pinfunction "2_2") (pintype "passive"))
      (node (ref "C18") (pin "2") (pinfunction "2_2") (pintype "passive"))
      (node (ref "C2") (pin "+") (pinfunction "+_+") (pintype "passive"))
      (node (ref "C20") (pin "2") (pinfunction "2_2") (pintype "passive"))
      (node (ref "C4") (pin "2") (pinfunction "2_2") (pintype "passive"))
      (node (ref "C5") (pin "2") (pinfunction "2_2") (pintype "passive"))
      (node (ref "C6") (pin "2") (pinfunction "2_2") (pintype "passive"))
      (node (ref "C8") (pin "2") (pinfunction "2_2") (pintype "passive"))
      (node (ref "C9") (pin "-") (pinfunction "-_-") (pintype "passive"))
      (node (ref "D1") (pin "C") (pinfunction "C_C") (pintype "passive"))
      (node (ref "D2") (pin "A") (pinfunction "A_A") (pintype "passive"))
      (node (ref "D3") (pin "A") (pinfunction "A_A") (pintype "passive"))
      (node (ref "D4") (pin "A") (pinfunction "A_A") (pintype "passive"))
      (node (ref "D8") (pin "A") (pinfunction "A_A") (pintype "passive"))
      (node (ref "D9") (pin "C") (pinfunction "C_C") (pintype "passive"))
      (node (ref "Q13") (pin "1") (pinfunction "E_1") (pintype "passive"))
      (node (ref "Q15") (pin "1") (pinfunction "E_1") (pintype "passive"))
      (node (ref "Q17") (pin "1") (pinfunction "E_1") (pintype "passive"))
      (node (ref "Q18") (pin "1") (pinfunction "E_1") (pintype "passive"))
      (node (ref "Q20") (pin "1") (pinfunction "E_1") (pintype "passive"))
      (node (ref "Q21") (pin "1") (pinfunction "E_1") (pintype "passive"))
      (node (ref "Q23") (pin "1") (pinfunction "E_1") (pintype "passive"))
      (node (ref "Q26") (pin "1") (pinfunction "E_1") (pintype "passive"))
      (node (ref "Q29") (pin "1") (pinfunction "E_1") (pintype "passive"))
      (node (ref "Q31") (pin "3") (pinfunction "C_3") (pintype "passive"))
      (node (ref "Q4") (pin "1") (pinfunction "E_1") (pintype "passive"))
      (node (ref "Q5") (pin "1") (pinfunction "E_1") (pintype "passive"))
      (node (ref "Q7") (pin "1") (pinfunction "E_1") (pintype "passive"))
      (node (ref "R4") (pin "2") (pinfunction "2_2") (pintype "passive"))
      (node (ref "R61") (pin "1") (pinfunction "1_1") (pintype "passive"))
      (node (ref "R62") (pin "1") (pinfunction "1_1") (pintype "passive"))
      (node (ref "R68") (pin "2") (pinfunction "2_2") (pintype "passive"))
      (node (ref "U$1") (pin "AC2") (pinfunction "1_AC2") (pintype "bidirectional"))
      (node (ref "U$1") (pin "AT1") (pinfunction "1_AT1") (pintype "bidirectional"))
      (node (ref "U$1") (pin "BC2") (pinfunction "1_BC2") (pintype "bidirectional"))
      (node (ref "U$1") (pin "BT1") (pinfunction "1_BT1") (pintype "bidirectional"))
    )
    (net (code "45") (name "Net-(E2A-I0)") (class "Default")
      (node (ref "D8") (pin "C") (pinfunction "C_C") (pintype "passive"))
      (node (ref "E2") (pin "1") (pinfunction "I0_1") (pintype "input"))
      (node (ref "E2") (pin "2") (pinfunction "I1_2") (pintype "input"))
      (node (ref "R37") (pin "2") (pinfunction "2_2") (pintype "passive"))
      (node (ref "R38") (pin "1") (pinfunction "1_1") (pintype "passive"))
    )
    (net (code "46") (name "Net-(E2B-I0)") (class "Default")
      (node (ref "D2") (pin "C") (pinfunction "C_C") (pintype "passive"))
      (node (ref "E2") (pin "4") (pinfunction "I0_4") (pintype "input"))
      (node (ref "E3") (pin "2") (pinfunction "P$2_2") (pintype "input"))
      (node (ref "R2") (pin "1") (pinfunction "1_1") (pintype "passive"))
      (node (ref "R3") (pin "2") (pinfunction "2_2") (pintype "passive"))
    )
    (net (code "47") (name "Net-(E2C-O)") (class "Default")
      (node (ref "E2") (pin "8") (pinfunction "O_8") (pintype "output"))
      (node (ref "E5") (pin "10") (pinfunction "I1_10") (pintype "input"))
    )
    (net (code "48") (name "Net-(E3A-P$3)") (class "Default")
      (node (ref "E3") (pin "3") (pinfunction "P$3_3") (pintype "input"))
      (node (ref "E3") (pin "4") (pinfunction "P$4_4") (pintype "input"))
      (node (ref "R73") (pin "1") (pinfunction "1_1") (pintype "passive"))
    )
    (net (code "49") (name "Net-(E3A-P$5)") (class "Default")
      (node (ref "C7") (pin "2") (pinfunction "2_2") (pintype "passive"))
      (node (ref "E3") (pin "11") (pinfunction "P$5_11") (pintype "bidirectional"))
    )
    (net (code "50") (name "Net-(E3A-P$6)") (class "Default")
      (node (ref "C7") (pin "1") (pinfunction "1_1") (pintype "passive"))
      (node (ref "E3") (pin "13") (pinfunction "P$6_13") (pintype "bidirectional"))
      (node (ref "R58") (pin "1") (pinfunction "1_1") (pintype "passive"))
    )
    (net (code "51") (name "Net-(E4A-I0)") (class "Default")
      (node (ref "E4") (pin "1") (pinfunction "I0_1") (pintype "input"))
      (node (ref "Q5") (pin "3") (pinfunction "C_3") (pintype "passive"))
      (node (ref "R16") (pin "1") (pinfunction "1_1") (pintype "passive"))
    )
    (net (code "52") (name "Net-(E4B-I0)") (class "Default")
      (node (ref "E4") (pin "4") (pinfunction "I0_4") (pintype "input"))
      (node (ref "Q7") (pin "3") (pinfunction "C_3") (pintype "passive"))
      (node (ref "R20") (pin "1") (pinfunction "1_1") (pintype "passive"))
    )
    (net (code "53") (name "Net-(E4C-I1)") (class "Default")
      (node (ref "E4") (pin "10") (pinfunction "I1_10") (pintype "input"))
      (node (ref "Q4") (pin "3") (pinfunction "C_3") (pintype "passive"))
      (node (ref "R12") (pin "1") (pinfunction "1_1") (pintype "passive"))
    )
    (net (code "54") (name "Net-(E4D-I1)") (class "Default")
      (node (ref "E4") (pin "13") (pinfunction "I1_13") (pintype "input"))
      (node (ref "R39") (pin "2") (pinfunction "2_2") (pintype "passive"))
    )
    (net (code "55") (name "Net-(E5A-I0)") (class "Default")
      (node (ref "D7") (pin "A") (pinfunction "A_A") (pintype "passive"))
      (node (ref "E5") (pin "4") (pinfunction "I0_4") (pintype "input"))
      (node (ref "R42") (pin "1") (pinfunction "1_1") (pintype "passive"))
    )
    (net (code "56") (name "Net-(E5A-O)") (class "Default")
      (node (ref "E5") (pin "3") (pinfunction "O_3") (pintype "output"))
      (node (ref "R53") (pin "1") (pinfunction "1_1") (pintype "passive"))
    )
    (net (code "57") (name "Net-(E5B-I0)") (class "Default")
      (node (ref "D5") (pin "A") (pinfunction "A_A") (pintype "passive"))
      (node (ref "E5") (pin "6") (pinfunction "I0_6") (pintype "input"))
      (node (ref "R40") (pin "1") (pinfunction "1_1") (pintype "passive"))
    )
    (net (code "58") (name "Net-(E5B-O)") (class "Default")
      (node (ref "E5") (pin "2") (pinfunction "O_2") (pintype "output"))
      (node (ref "R43") (pin "1") (pinfunction "1_1") (pintype "passive"))
    )
    (net (code "59") (name "Net-(E5C-O)") (class "Default")
      (node (ref "E5") (pin "14") (pinfunction "O_14") (pintype "output"))
      (node (ref "R29") (pin "1") (pinfunction "1_1") (pintype "passive"))
    )
    (net (code "60") (name "Net-(E5D-I0)") (class "Default")
      (node (ref "D6") (pin "A") (pinfunction "A_A") (pintype "passive"))
      (node (ref "E5") (pin "11") (pinfunction "I0_11") (pintype "input"))
      (node (ref "R41") (pin "1") (pinfunction "1_1") (pintype "passive"))
    )
    (net (code "61") (name "Net-(E5D-O)") (class "Default")
      (node (ref "E5") (pin "13") (pinfunction "O_13") (pintype "output"))
      (node (ref "R48") (pin "1") (pinfunction "1_1") (pintype "passive"))
    )
    (net (code "62") (name "Net-(Q1-B)") (class "Default")
      (node (ref "D1") (pin "A") (pinfunction "A_A") (pintype "passive"))
      (node (ref "Q1") (pin "2") (pinfunction "B_2") (pintype "passive"))
      (node (ref "Q31") (pin "2") (pinfunction "B_2") (pintype "passive"))
      (node (ref "R72") (pin "2") (pinfunction "2_2") (pintype "passive"))
    )
    (net (code "63") (name "Net-(Q1-C)") (class "Default")
      (node (ref "Q1") (pin "3") (pinfunction "C_3") (pintype "passive"))
      (node (ref "R6") (pin "2") (pinfunction "2_2") (pintype "passive"))
    )
    (net (code "64") (name "Net-(Q2-B)") (class "Default")
      (node (ref "Q2") (pin "2") (pinfunction "B_2") (pintype "passive"))
      (node (ref "R1") (pin "2") (pinfunction "2_2") (pintype "passive"))
    )
    (net (code "65") (name "Net-(Q2-C)") (class "Default")
      (node (ref "Q2") (pin "3") (pinfunction "C_3") (pintype "passive"))
      (node (ref "R3") (pin "1") (pinfunction "1_1") (pintype "passive"))
    )
    (net (code "66") (name "Net-(Q3-B)") (class "Default")
      (node (ref "Q3") (pin "2") (pinfunction "B_2") (pintype "passive"))
      (node (ref "R10") (pin "2") (pinfunction "2_2") (pintype "passive"))
    )
    (net (code "67") (name "Net-(Q3-C)") (class "Default")
      (node (ref "Q3") (pin "3") (pinfunction "C_3") (pintype "passive"))
      (node (ref "Q4") (pin "2") (pinfunction "B_2") (pintype "passive"))
      (node (ref "R11") (pin "1") (pinfunction "1_1") (pintype "passive"))
    )
    (net (code "68") (name "Net-(Q6-B)") (class "Default")
      (node (ref "Q6") (pin "2") (pinfunction "B_2") (pintype "passive"))
      (node (ref "R18") (pin "2") (pinfunction "2_2") (pintype "passive"))
    )
    (net (code "69") (name "Net-(Q6-C)") (class "Default")
      (node (ref "Q6") (pin "3") (pinfunction "C_3") (pintype "passive"))
      (node (ref "Q7") (pin "2") (pinfunction "B_2") (pintype "passive"))
      (node (ref "R19") (pin "1") (pinfunction "1_1") (pintype "passive"))
    )
    (net (code "70") (name "Net-(Q10-B)") (class "Default")
      (node (ref "Q10") (pin "2") (pinfunction "B_2") (pintype "passive"))
      (node (ref "R33") (pin "2") (pinfunction "2_2") (pintype "passive"))
    )
    (net (code "71") (name "Net-(Q10-C)") (class "Default")
      (node (ref "Q10") (pin "3") (pinfunction "C_3") (pintype "passive"))
      (node (ref "R35") (pin "1") (pinfunction "1_1") (pintype "passive"))
    )
    (net (code "72") (name "Net-(Q11-B)") (class "Default")
      (node (ref "Q11") (pin "2") (pinfunction "B_2") (pintype "passive"))
      (node (ref "R32") (pin "2") (pinfunction "2_2") (pintype "passive"))
    )
    (net (code "73") (name "Net-(Q11-C)") (class "Default")
      (node (ref "Q11") (pin "3") (pinfunction "C_3") (pintype "passive"))
      (node (ref "R31") (pin "1") (pinfunction "1_1") (pintype "passive"))
    )
    (net (code "74") (name "Net-(Q12-B)") (class "Default")
      (node (ref "Q12") (pin "2") (pinfunction "B_2") (pintype "passive"))
      (node (ref "R36") (pin "2") (pinfunction "2_2") (pintype "passive"))
    )
    (net (code "75") (name "Net-(Q12-C)") (class "Default")
      (node (ref "Q12") (pin "3") (pinfunction "C_3") (pintype "passive"))
      (node (ref "R37") (pin "1") (pinfunction "1_1") (pintype "passive"))
    )
    (net (code "76") (name "Net-(Q13-B)") (class "Default")
      (node (ref "Q13") (pin "2") (pinfunction "B_2") (pintype "passive"))
      (node (ref "R28") (pin "1") (pinfunction "1_1") (pintype "passive"))
      (node (ref "R29") (pin "2") (pinfunction "2_2") (pintype "passive"))
    )
    (net (code "77") (name "Net-(Q15-B)") (class "Default")
      (node (ref "Q15") (pin "2") (pinfunction "B_2") (pintype "passive"))
      (node (ref "R43") (pin "2") (pinfunction "2_2") (pintype "passive"))
      (node (ref "R44") (pin "1") (pinfunction "1_1") (pintype "passive"))
    )
    (net (code "78") (name "Net-(Q16-B)") (class "Default")
      (node (ref "C15") (pin "1") (pinfunction "1_1") (pintype "passive"))
      (node (ref "Q16") (pin "2") (pinfunction "B_2") (pintype "passive"))
      (node (ref "R45") (pin "2") (pinfunction "2_2") (pintype "passive"))
    )
    (net (code "79") (name "Net-(Q16-C)") (class "Default")
      (node (ref "C16") (pin "1") (pinfunction "1_1") (pintype "passive"))
      (node (ref "Q16") (pin "3") (pinfunction "C_3") (pintype "passive"))
      (node (ref "Q17") (pin "2") (pinfunction "B_2") (pintype "passive"))
      (node (ref "R46") (pin "1") (pinfunction "1_1") (pintype "passive"))
    )
    (net (code "80") (name "Net-(Q18-B)") (class "Default")
      (node (ref "Q18") (pin "2") (pinfunction "B_2") (pintype "passive"))
      (node (ref "R48") (pin "2") (pinfunction "2_2") (pintype "passive"))
      (node (ref "R49") (pin "1") (pinfunction "1_1") (pintype "passive"))
    )
    (net (code "81") (name "Net-(Q19-B)") (class "Default")
      (node (ref "C17") (pin "1") (pinfunction "1_1") (pintype "passive"))
      (node (ref "Q19") (pin "2") (pinfunction "B_2") (pintype "passive"))
      (node (ref "R50") (pin "2") (pinfunction "2_2") (pintype "passive"))
    )
    (net (code "82") (name "Net-(Q19-C)") (class "Default")
      (node (ref "C18") (pin "1") (pinfunction "1_1") (pintype "passive"))
      (node (ref "Q19") (pin "3") (pinfunction "C_3") (pintype "passive"))
      (node (ref "Q20") (pin "2") (pinfunction "B_2") (pintype "passive"))
      (node (ref "R51") (pin "1") (pinfunction "1_1") (pintype "passive"))
    )
    (net (code "83") (name "Net-(Q21-B)") (class "Default")
      (node (ref "Q21") (pin "2") (pinfunction "B_2") (pintype "passive"))
      (node (ref "R53") (pin "2") (pinfunction "2_2") (pintype "passive"))
      (node (ref "R54") (pin "1") (pinfunction "1_1") (pintype "passive"))
    )
    (net (code "84") (name "Net-(Q22-B)") (class "Default")
      (node (ref "C19") (pin "1") (pinfunction "1_1") (pintype "passive"))
      (node (ref "Q22") (pin "2") (pinfunction "B_2") (pintype "passive"))
      (node (ref "R55") (pin "2") (pinfunction "2_2") (pintype "passive"))
    )
    (net (code "85") (name "Net-(Q22-C)") (class "Default")
      (node (ref "C20") (pin "1") (pinfunction "1_1") (pintype "passive"))
      (node (ref "Q22") (pin "3") (pinfunction "C_3") (pintype "passive"))
      (node (ref "Q23") (pin "2") (pinfunction "B_2") (pintype "passive"))
      (node (ref "R56") (pin "1") (pinfunction "1_1") (pintype "passive"))
    )
    (net (code "86") (name "Net-(Q24-B)") (class "Default")
      (node (ref "Q24") (pin "2") (pinfunction "B_2") (pintype "passive"))
      (node (ref "R59") (pin "1") (pinfunction "1_1") (pintype "passive"))
      (node (ref "R61") (pin "2") (pinfunction "2_2") (pintype "passive"))
    )
    (net (code "87") (name "Net-(Q24-C)") (class "Default")
      (node (ref "Q24") (pin "3") (pinfunction "C_3") (pintype "passive"))
      (node (ref "R60") (pin "1") (pinfunction "1_1") (pintype "passive"))
    )
    (net (code "88") (name "Net-(Q25-B)") (class "Default")
      (node (ref "Q25") (pin "2") (pinfunction "B_2") (pintype "passive"))
      (node (ref "R66") (pin "2") (pinfunction "2_2") (pintype "passive"))
    )
    (net (code "89") (name "Net-(Q25-C)") (class "Default")
      (node (ref "Q25") (pin "3") (pinfunction "C_3") (pintype "passive"))
      (node (ref "R65") (pin "1") (pinfunction "1_1") (pintype "passive"))
    )
    (net (code "90") (name "Net-(Q25-E)") (class "Default")
      (node (ref "D10") (pin "A") (pinfunction "A_A") (pintype "passive"))
      (node (ref "Q25") (pin "1") (pinfunction "E_1") (pintype "passive"))
    )
    (net (code "91") (name "Net-(Q26-B)") (class "Default")
      (node (ref "Q26") (pin "2") (pinfunction "B_2") (pintype "passive"))
      (node (ref "R63") (pin "1") (pinfunction "1_1") (pintype "passive"))
      (node (ref "R65") (pin "2") (pinfunction "2_2") (pintype "passive"))
    )
    (net (code "92") (name "Net-(Q27-B)") (class "Default")
      (node (ref "D10") (pin "C") (pinfunction "C_C") (pintype "passive"))
      (node (ref "Q27") (pin "2") (pinfunction "B_2") (pintype "passive"))
      (node (ref "R67") (pin "2") (pinfunction "2_2") (pintype "passive"))
    )
    (net (code "93") (name "Net-(Q28-B)") (class "Default")
      (node (ref "Q28") (pin "2") (pinfunction "B_2") (pintype "passive"))
      (node (ref "R69") (pin "2") (pinfunction "2_2") (pintype "passive"))
    )
    (net (code "94") (name "Net-(Q28-C)") (class "Default")
      (node (ref "Q28") (pin "3") (pinfunction "C_3") (pintype "passive"))
      (node (ref "Q29") (pin "2") (pinfunction "B_2") (pintype "passive"))
      (node (ref "R70") (pin "1") (pinfunction "1_1") (pintype "passive"))
    )
    (net (code "95") (name "Net-(Q30-B)") (class "Default")
      (node (ref "Q30") (pin "2") (pinfunction "B_2") (pintype "passive"))
      (node (ref "R14") (pin "2") (pinfunction "2_2") (pintype "passive"))
    )
    (net (code "96") (name "Net-(Q30-C)") (class "Default")
      (node (ref "Q30") (pin "3") (pinfunction "C_3") (pintype "passive"))
      (node (ref "Q5") (pin "2") (pinfunction "B_2") (pintype "passive"))
      (node (ref "R15") (pin "1") (pinfunction "1_1") (pintype "passive"))
    )
    (net (code "97") (name "Net-(U$1BB-1)") (class "Default")
      (node (ref "D4") (pin "C") (pinfunction "C_C") (pintype "passive"))
      (node (ref "R30") (pin "1") (pinfunction "1_1") (pintype "passive"))
      (node (ref "R31") (pin "2") (pinfunction "2_2") (pintype "passive"))
      (node (ref "U$1") (pin "BK2") (pinfunction "1_BK2") (pintype "bidirectional"))
    )
    (net (code "98") (name "VCC") (class "Default")
      (node (ref "C10") (pin "1") (pinfunction "1_1") (pintype "passive"))
      (node (ref "C11") (pin "1") (pinfunction "1_1") (pintype "passive"))
      (node (ref "C12") (pin "1") (pinfunction "1_1") (pintype "passive"))
      (node (ref "C13") (pin "1") (pinfunction "1_1") (pintype "passive"))
      (node (ref "C14") (pin "1") (pinfunction "1_1") (pintype "passive"))
      (node (ref "R11") (pin "2") (pinfunction "2_2") (pintype "passive"))
      (node (ref "R12") (pin "2") (pinfunction "2_2") (pintype "passive"))
      (node (ref "R13") (pin "2") (pinfunction "2_2") (pintype "passive"))
      (node (ref "R15") (pin "2") (pinfunction "2_2") (pintype "passive"))
      (node (ref "R16") (pin "2") (pinfunction "2_2") (pintype "passive"))
      (node (ref "R17") (pin "2") (pinfunction "2_2") (pintype "passive"))
      (node (ref "R19") (pin "2") (pinfunction "2_2") (pintype "passive"))
      (node (ref "R2") (pin "2") (pinfunction "2_2") (pintype "passive"))
      (node (ref "R20") (pin "2") (pinfunction "2_2") (pintype "passive"))
      (node (ref "R21") (pin "2") (pinfunction "2_2") (pintype "passive"))
      (node (ref "R25") (pin "2") (pinfunction "2_2") (pintype "passive"))
      (node (ref "R26") (pin "2") (pinfunction "2_2") (pintype "passive"))
      (node (ref "R27") (pin "2") (pinfunction "2_2") (pintype "passive"))
      (node (ref "R30") (pin "2") (pinfunction "2_2") (pintype "passive"))
      (node (ref "R34") (pin "2") (pinfunction "2_2") (pintype "passive"))
      (node (ref "R38") (pin "2") (pinfunction "2_2") (pintype "passive"))
      (node (ref "R39") (pin "1") (pinfunction "1_1") (pintype "passive"))
      (node (ref "R40") (pin "2") (pinfunction "2_2") (pintype "passive"))
      (node (ref "R41") (pin "2") (pinfunction "2_2") (pintype "passive"))
      (node (ref "R42") (pin "2") (pinfunction "2_2") (pintype "passive"))
      (node (ref "R46") (pin "2") (pinfunction "2_2") (pintype "passive"))
      (node (ref "R47") (pin "2") (pinfunction "2_2") (pintype "passive"))
      (node (ref "R51") (pin "2") (pinfunction "2_2") (pintype "passive"))
      (node (ref "R52") (pin "2") (pinfunction "2_2") (pintype "passive"))
      (node (ref "R56") (pin "2") (pinfunction "2_2") (pintype "passive"))
      (node (ref "R57") (pin "2") (pinfunction "2_2") (pintype "passive"))
      (node (ref "R58") (pin "2") (pinfunction "2_2") (pintype "passive"))
      (node (ref "R59") (pin "2") (pinfunction "2_2") (pintype "passive"))
      (node (ref "R60") (pin "2") (pinfunction "2_2") (pintype "passive"))
      (node (ref "R63") (pin "2") (pinfunction "2_2") (pintype "passive"))
      (node (ref "R64") (pin "2") (pinfunction "2_2") (pintype "passive"))
      (node (ref "R70") (pin "2") (pinfunction "2_2") (pintype "passive"))
      (node (ref "R71") (pin "2") (pinfunction "2_2") (pintype "passive"))
      (node (ref "R73") (pin "2") (pinfunction "2_2") (pintype "passive"))
      (node (ref "R8") (pin "2") (pinfunction "2_2") (pintype "passive"))
      (node (ref "U$1") (pin "AA2") (pinfunction "1_AA2") (pintype "bidirectional"))
      (node (ref "U$1") (pin "BA2") (pinfunction "1_BA2") (pintype "bidirectional"))
    )
  )
)
